# usb-debug.net
KiCad netlist of a schematic drawn in Altium Designer
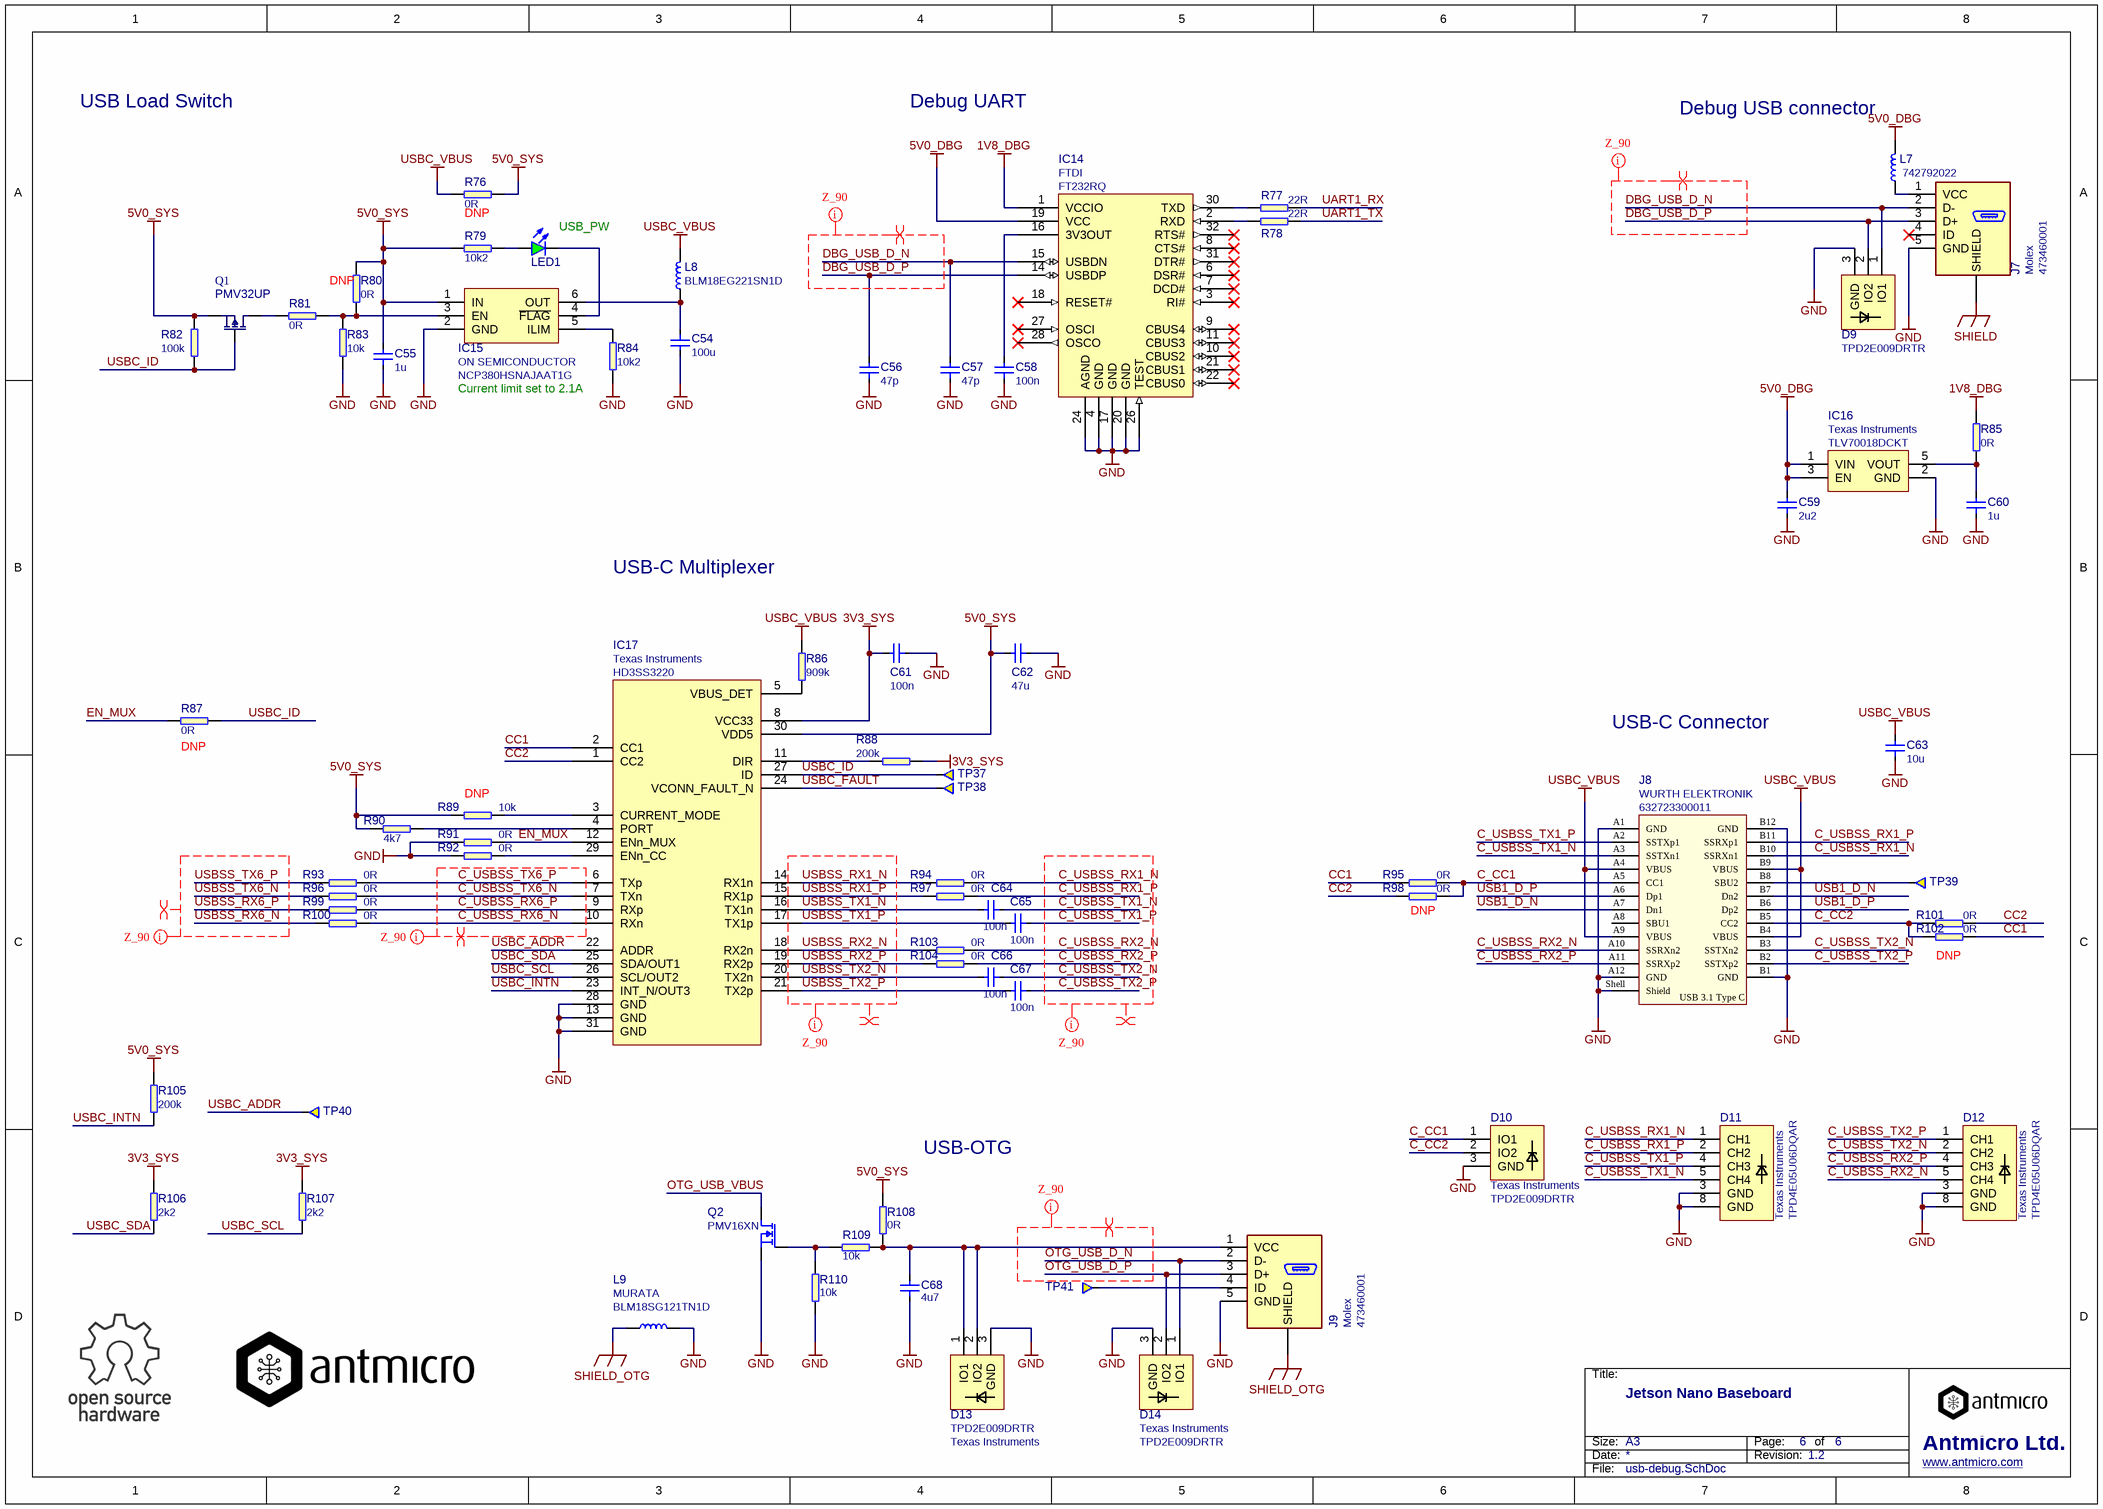
[diagram p0: usb-debug.SchDoc]

(export (version "E")
  (design (tool "Eeschema 10.0.6"))
  (components
    (comp (ref "C54")
      (value "100u")
      (footprint "1210")
      (description "MLCC SMT Capacitor 100uF 1210")
      (fields (field (name "MANUFACTURER") "SAMSUNG") (field (name "PARTNUMBER") "C_100u_1210"))
      (libsource (lib "jetson-nano-baseboard") (part "C_100u_1210"))
    )
    (comp (ref "C55")
      (value "1u")
      (footprint "0603")
      (description "MLCC SMT Capacitor 1uF 0603")
      (fields (field (name "MANUFACTURER") "KEMET") (field (name "PARTNUMBER") "C_1u_0603"))
      (libsource (lib "jetson-nano-baseboard") (part "C_1u_0603"))
    )
    (comp (ref "C56")
      (value "47p")
      (footprint "0603")
      (description "MLCC SMT Capacitor 47pF 0603")
      (fields (field (name "MANUFACTURER") "AVX") (field (name "PARTNUMBER") "C_47p_0603"))
      (libsource (lib "jetson-nano-baseboard") (part "C_47p_0603"))
    )
    (comp (ref "C57")
      (value "47p")
      (footprint "0603")
      (description "MLCC SMT Capacitor 47pF 0603")
      (fields (field (name "MANUFACTURER") "AVX") (field (name "PARTNUMBER") "C_47p_0603"))
      (libsource (lib "jetson-nano-baseboard") (part "C_47p_0603"))
    )
    (comp (ref "C58")
      (value "100n")
      (footprint "0603")
      (description "MLCC SMT Capacitor 100nF 0603")
      (fields (field (name "MANUFACTURER") "AVX") (field (name "PARTNUMBER") "C_100n_0603"))
      (libsource (lib "jetson-nano-baseboard") (part "C_100n_0603"))
    )
    (comp (ref "C59")
      (value "2u2")
      (footprint "0402")
      (description "MLCC SMT Capacitor 2.2uF 0402")
      (fields (field (name "MANUFACTURER") "TDK") (field (name "PARTNUMBER") "C_2u2_0402"))
      (libsource (lib "jetson-nano-baseboard") (part "C_2u2_0402"))
    )
    (comp (ref "C60")
      (value "1u")
      (footprint "0402")
      (description "MLCC SMT Capacitor 1uF 0402")
      (fields (field (name "MANUFACTURER") "MULTICOMP") (field (name "PARTNUMBER") "C_1u_0402"))
      (libsource (lib "jetson-nano-baseboard") (part "C_1u_0402"))
    )
    (comp (ref "C61")
      (value "100n")
      (footprint "0603")
      (description "MLCC SMT Capacitor 100nF 0603")
      (fields (field (name "MANUFACTURER") "AVX") (field (name "PARTNUMBER") "C_100n_0603"))
      (libsource (lib "jetson-nano-baseboard") (part "C_100n_0603"))
    )
    (comp (ref "C62")
      (value "47u")
      (footprint "0805")
      (description "MLCC SMT Capacitor 47uF 0805")
      (fields (field (name "PARTNUMBER") "C_47u_0805") (field (name "MANUFACTURER") "KEMET"))
      (libsource (lib "jetson-nano-baseboard") (part "C_47u_0805"))
    )
    (comp (ref "C63")
      (value "10u")
      (footprint "0603")
      (description "MLCC SMT Capacitor 10uF 0603")
      (fields (field (name "PARTNUMBER") "C_10u_0603") (field (name "MANUFACTURER") "Walsin"))
      (libsource (lib "jetson-nano-baseboard") (part "C_10u_0603"))
    )
    (comp (ref "C64")
      (value "100n")
      (footprint "0402")
      (description "MLCC SMT Capacitor 100n 0402")
      (fields (field (name "MANUFACTURER") "TDK") (field (name "PARTNUMBER") "C_100n_0402"))
      (libsource (lib "jetson-nano-baseboard") (part "C_100n_0402"))
    )
    (comp (ref "C65")
      (value "100n")
      (footprint "0402")
      (description "MLCC SMT Capacitor 100n 0402")
      (fields (field (name "MANUFACTURER") "TDK") (field (name "PARTNUMBER") "C_100n_0402"))
      (libsource (lib "jetson-nano-baseboard") (part "C_100n_0402"))
    )
    (comp (ref "C66")
      (value "100n")
      (footprint "0402")
      (description "MLCC SMT Capacitor 100n 0402")
      (fields (field (name "MANUFACTURER") "TDK") (field (name "PARTNUMBER") "C_100n_0402"))
      (libsource (lib "jetson-nano-baseboard") (part "C_100n_0402"))
    )
    (comp (ref "C67")
      (value "100n")
      (footprint "0402")
      (description "MLCC SMT Capacitor 100n 0402")
      (fields (field (name "MANUFACTURER") "TDK") (field (name "PARTNUMBER") "C_100n_0402"))
      (libsource (lib "jetson-nano-baseboard") (part "C_100n_0402"))
    )
    (comp (ref "C68")
      (value "4u7")
      (footprint "0603")
      (description "MLCC SMT Capacitor 4.7uF 0603")
      (fields (field (name "PARTNUMBER") "C_4u7_0603") (field (name "MANUFACTURER") "MULTICOMP"))
      (libsource (lib "jetson-nano-baseboard") (part "C_4u7_0603"))
    )
    (comp (ref "D9")
      (value "TPD2E009DRTR")
      (footprint "SOT-3")
      (description "ESD Suppressors 2-CH")
      (fields (field (name "MANUFACTURER") "Texas Instruments"))
      (libsource (lib "") (part "TPD2E009_2"))
    )
    (comp (ref "D10")
      (value "TPD2E009DRTR")
      (footprint "SOT-3")
      (description "ESD Suppressors 2-CH")
      (fields (field (name "MANUFACTURER") "Texas Instruments"))
      (libsource (lib "") (part "TPD2E009_1"))
    )
    (comp (ref "D11")
      (value "TPD4E05U06")
      (footprint "TPD4E05U06_PASS")
      (description "ESD Suppressors 4-CH")
      (fields
        (field (name "PARTNUMBER") "TPD4E05U06_PASS")
        (field (name "MANUFACTURER") "Texas Instruments")
        (field (name "PARTSYMBOL") "TPD4E05U06DQAR")
      )
      (libsource (lib "jetson-nano-baseboard") (part "TPD4E05U06"))
    )
    (comp (ref "D12")
      (value "TPD4E05U06")
      (footprint "TPD4E05U06_PASS")
      (description "ESD Suppressors 4-CH")
      (fields
        (field (name "PARTNUMBER") "TPD4E05U06_PASS")
        (field (name "MANUFACTURER") "Texas Instruments")
        (field (name "PARTSYMBOL") "TPD4E05U06DQAR")
      )
      (libsource (lib "jetson-nano-baseboard") (part "TPD4E05U06"))
    )
    (comp (ref "D13")
      (value "TPD2E009DRTR")
      (footprint "SOT-3")
      (description "ESD Suppressors 2-CH")
      (fields (field (name "MANUFACTURER") "Texas Instruments"))
      (libsource (lib "jetson-nano-baseboard") (part "TPD2E009"))
    )
    (comp (ref "D14")
      (value "TPD2E009DRTR")
      (footprint "SOT-3")
      (description "ESD Suppressors 2-CH")
      (fields (field (name "MANUFACTURER") "Texas Instruments"))
      (libsource (lib "") (part "TPD2E009_2"))
    )
    (comp (ref "IC14")
      (value "FT232RQ")
      (footprint "QFN-32")
      (description "USB to serial UART interface")
      (fields (field (name "MANUFACTURER") "FTDI") (field (name "PARTNUMBER") "FT232RQ"))
      (libsource (lib "jetson-nano-baseboard") (part "FT232RQ"))
    )
    (comp (ref "IC15")
      (value "NCP380HSNAJAAT1G")
      (footprint "TSOP-6")
      (description "POWER LOAD SWITCH, HIGH SIDE")
      (fields (field (name "MANUFACTURER") "ON SEMICONDUCTOR"))
      (libsource (lib "jetson-nano-baseboard") (part "NCP380HSNAJAAT1G"))
    )
    (comp (ref "IC16")
      (value "TLV70018DCKT")
      (footprint "SC70-5")
      (description "Voltage Regulator, 2V to 5.5V, 175mV Dropout, 1.8Vout, 200mAout")
      (fields (field (name "MANUFACTURER") "Texas Instruments"))
      (libsource (lib "jetson-nano-baseboard") (part "TLV700"))
    )
    (comp (ref "IC17")
      (value "HD3SS3220")
      (footprint "RNH0030A")
      (description "IC DRP PORT CTLR USB-C 30WQFN")
      (fields (field (name "MANUFACTURER") "Texas Instruments"))
      (libsource (lib "jetson-nano-baseboard") (part "HD3SS3220"))
    )
    (comp (ref "J7")
      (value "Molex 47346-0001")
      (footprint "CON-Molex-047346-0001")
      (description "USB - micro B Receptacle Connector 5 Position Surface Mount, Right Angle, Horizontal")
      (fields
        (field (name "PARTNUMBER") "CON-Molex-47346-0001")
        (field (name "MANUFACTURER") "Molex")
        (field (name "PARTSYMBOL") "473460001")
      )
      (libsource (lib "jetson-nano-baseboard") (part "Micro USB B"))
    )
    (comp (ref "J8")
      (value "632723300011")
      (footprint "WE_632723300011")
      (description "USB 3.1 Type C Receptacle Horizontal THR WR-COM")
      (fields (field (name "PARTNUMBER") "WE_632723300011") (field (name "MANUFACTURER") "WURTH ELEKTRONIK"))
      (libsource (lib "jetson-nano-baseboard") (part "WE_632723300011"))
    )
    (comp (ref "J9")
      (value "Molex 47346-0001")
      (footprint "CON-Molex-047346-0001")
      (description "USB - micro B Receptacle Connector 5 Position Surface Mount, Right Angle, Horizontal")
      (fields
        (field (name "PARTNUMBER") "CON-Molex-47346-0001")
        (field (name "MANUFACTURER") "Molex")
        (field (name "PARTSYMBOL") "473460001")
      )
      (libsource (lib "jetson-nano-baseboard") (part "Micro USB B"))
    )
    (comp (ref "L7")
      (value "742792022")
      (footprint "0805")
      (description "MURATA  BLM18EG221SN1D  FERRITE BEAD, 0.05OHM, 2A, 0603")
      (fields (field (name "MANUFACTURER") "WURTH ELEKTRONIK"))
      (libsource (lib "jetson-nano-baseboard") (part "742792022"))
    )
    (comp (ref "L8")
      (value "BLM18EG221SN1D")
      (footprint "0603")
      (description "MURATA  BLM18EG221SN1D  FERRITE BEAD, 0.05OHM, 2A, 0603")
      (fields (field (name "MANUFACTURER") "MURATA"))
      (libsource (lib "jetson-nano-baseboard") (part "BLM18EG221SN1D"))
    )
    (comp (ref "L9")
      (value "BLM18SG121TN1D")
      (footprint "0603")
      (description "FERRITE BEAD, 0.025OHM, 3A, 0603")
      (fields (field (name "MANUFACTURER") "MURATA"))
      (libsource (lib "jetson-nano-baseboard") (part "BLM18SG121TN1D"))
    )
    (comp (ref "LED1")
      (value "KPT-1608SGC")
      (footprint "LED0603")
      (description "LED Green 0603 case")
      (fields (field (name "MANUFACTURER") "KINGBRIGHT") (field (name "PARTNUMBER") "LED_G"))
      (libsource (lib "jetson-nano-baseboard") (part "LED"))
    )
    (comp (ref "Q1")
      (value "PMV32UP")
      (footprint "SOT-23")
      (description "P CH, 20V, 4A")
      (fields (field (name "MANUFACTURER") "NXP"))
      (libsource (lib "jetson-nano-baseboard") (part "PMOS"))
    )
    (comp (ref "Q2")
      (value "PMV16XN")
      (footprint "SOT-23")
      (description "MOSFET, N CH")
      (fields (field (name "MANUFACTURER") "NXP"))
      (libsource (lib "jetson-nano-baseboard") (part "NMOS_PMV16XN"))
    )
    (comp (ref "R76")
      (value "0R")
      (footprint "0603")
      (description "RES, 0R, 0603")
      (fields (field (name "MANUFACTURER") "BOURNS") (field (name "PARTNUMBER") "R_0R_0603"))
      (libsource (lib "jetson-nano-baseboard") (part "R_0R_0603"))
    )
    (comp (ref "R77")
      (value "22R")
      (footprint "0402")
      (description "RES, 22R, 0402")
      (fields (field (name "MANUFACTURER") "VISHAY") (field (name "PARTNUMBER") "R_22R_0402"))
      (libsource (lib "jetson-nano-baseboard") (part "R_22R_0402"))
    )
    (comp (ref "R78")
      (value "22R")
      (footprint "0402")
      (description "RES, 22R, 0402")
      (fields (field (name "MANUFACTURER") "VISHAY") (field (name "PARTNUMBER") "R_22R_0402"))
      (libsource (lib "jetson-nano-baseboard") (part "R_22R_0402"))
    )
    (comp (ref "R79")
      (value "10k2")
      (footprint "0603")
      (description "RES, 470R, 0603")
      (fields (field (name "MANUFACTURER") "BOURNS") (field (name "PARTNUMBER") "R_470R_0603"))
      (libsource (lib "jetson-nano-baseboard") (part "R_470R_0603"))
    )
    (comp (ref "R80")
      (value "0R")
      (footprint "0402")
      (description "RES, 0R, 0402")
      (fields (field (name "PARTNUMBER") "R_0R_0402") (field (name "MANUFACTURER") "Panasonic"))
      (libsource (lib "") (part "R_0R_0402_1"))
    )
    (comp (ref "R81")
      (value "0R")
      (footprint "0402")
      (description "RES, 0R, 0402")
      (fields (field (name "PARTNUMBER") "R_0R_0402") (field (name "MANUFACTURER") "Panasonic"))
      (libsource (lib "jetson-nano-baseboard") (part "R_0R_0402"))
    )
    (comp (ref "R82")
      (value "100k")
      (footprint "0603")
      (description "RES, 100k, 0603")
      (fields (field (name "MANUFACTURER") "BOURNS") (field (name "PARTNUMBER") "R_100k_0603"))
      (libsource (lib "jetson-nano-baseboard") (part "R_100k_0603"))
    )
    (comp (ref "R83")
      (value "10k")
      (footprint "0402")
      (description "RES, 10k, 0402")
      (fields (field (name "MANUFACTURER") "MULTICOMP") (field (name "PARTNUMBER") "R_10k_0402"))
      (libsource (lib "") (part "R_10k_0402_2"))
    )
    (comp (ref "R84")
      (value "10k2")
      (footprint "0603")
      (description "RES, 5k6, 0603")
      (fields (field (name "PARTNUMBER") "R_5k6_0603") (field (name "MANUFACTURER") "Panasonic"))
      (libsource (lib "jetson-nano-baseboard") (part "R_5k6_0603"))
    )
    (comp (ref "R85")
      (value "0R")
      (footprint "0603")
      (description "RES, 0R, 0603")
      (fields (field (name "MANUFACTURER") "BOURNS") (field (name "PARTNUMBER") "R_0R_0603"))
      (libsource (lib "") (part "R_0R_0603_1"))
    )
    (comp (ref "R86")
      (value "909k")
      (footprint "0402")
      (description "RES, 909k, 0402")
      (fields (field (name "PARTNUMBER") "R_909k_0402") (field (name "MANUFACTURER") "Panasonic"))
      (libsource (lib "jetson-nano-baseboard") (part "R_909k_0402"))
    )
    (comp (ref "R87")
      (value "0R")
      (footprint "0402")
      (description "RES, 0R, 0402")
      (fields (field (name "PARTNUMBER") "R_0R_0402") (field (name "MANUFACTURER") "Panasonic"))
      (libsource (lib "jetson-nano-baseboard") (part "R_0R_0402"))
    )
    (comp (ref "R88")
      (value "200k")
      (footprint "0402")
      (description "RES, 200k, 0402")
      (fields (field (name "PARTNUMBER") "R_200k_0402") (field (name "MANUFACTURER") "YAGEO"))
      (libsource (lib "") (part "R_200k_0402_1"))
    )
    (comp (ref "R89")
      (value "10k")
      (footprint "0402")
      (description "RES, 10k, 0402")
      (fields (field (name "PARTNUMBER") "R_10k_0402") (field (name "MANUFACTURER") "MULTICOMP"))
      (libsource (lib "") (part "R_10k_0402_1"))
    )
    (comp (ref "R90")
      (value "4k7")
      (footprint "0402")
      (description "RES, 4k7, 0402")
      (fields (field (name "PARTNUMBER") "R_4k7_0402") (field (name "MANUFACTURER") "Panasonic"))
      (libsource (lib "jetson-nano-baseboard") (part "R_4k7_0402"))
    )
    (comp (ref "R91")
      (value "0R")
      (footprint "0402")
      (description "RES, 0R, 0402")
      (fields (field (name "PARTNUMBER") "R_0R_0402") (field (name "MANUFACTURER") "Panasonic"))
      (libsource (lib "jetson-nano-baseboard") (part "R_0R_0402"))
    )
    (comp (ref "R92")
      (value "0R")
      (footprint "0402")
      (description "RES, 0R, 0402")
      (fields (field (name "PARTNUMBER") "R_0R_0402") (field (name "MANUFACTURER") "Panasonic"))
      (libsource (lib "jetson-nano-baseboard") (part "R_0R_0402"))
    )
    (comp (ref "R93")
      (value "0R")
      (footprint "0402")
      (description "RES, 0R, 0402")
      (fields (field (name "PARTNUMBER") "R_0R_0402") (field (name "MANUFACTURER") "Panasonic"))
      (libsource (lib "jetson-nano-baseboard") (part "R_0R_0402"))
    )
    (comp (ref "R94")
      (value "0R")
      (footprint "0402")
      (description "RES, 0R, 0402")
      (fields (field (name "PARTNUMBER") "R_0R_0402") (field (name "MANUFACTURER") "Panasonic"))
      (libsource (lib "jetson-nano-baseboard") (part "R_0R_0402"))
    )
    (comp (ref "R95")
      (value "0R")
      (footprint "0402")
      (description "RES, 0R, 0402")
      (fields (field (name "PARTNUMBER") "R_0R_0402") (field (name "MANUFACTURER") "Panasonic"))
      (libsource (lib "jetson-nano-baseboard") (part "R_0R_0402"))
    )
    (comp (ref "R96")
      (value "0R")
      (footprint "0402")
      (description "RES, 0R, 0402")
      (fields (field (name "PARTNUMBER") "R_0R_0402") (field (name "MANUFACTURER") "Panasonic"))
      (libsource (lib "jetson-nano-baseboard") (part "R_0R_0402"))
    )
    (comp (ref "R97")
      (value "0R")
      (footprint "0402")
      (description "RES, 0R, 0402")
      (fields (field (name "PARTNUMBER") "R_0R_0402") (field (name "MANUFACTURER") "Panasonic"))
      (libsource (lib "jetson-nano-baseboard") (part "R_0R_0402"))
    )
    (comp (ref "R98")
      (value "0R")
      (footprint "0402")
      (description "RES, 0R, 0402")
      (fields (field (name "PARTNUMBER") "R_0R_0402") (field (name "MANUFACTURER") "Panasonic"))
      (libsource (lib "jetson-nano-baseboard") (part "R_0R_0402"))
    )
    (comp (ref "R99")
      (value "0R")
      (footprint "0402")
      (description "RES, 0R, 0402")
      (fields (field (name "PARTNUMBER") "R_0R_0402") (field (name "MANUFACTURER") "Panasonic"))
      (libsource (lib "jetson-nano-baseboard") (part "R_0R_0402"))
    )
    (comp (ref "R100")
      (value "0R")
      (footprint "0402")
      (description "RES, 0R, 0402")
      (fields (field (name "PARTNUMBER") "R_0R_0402") (field (name "MANUFACTURER") "Panasonic"))
      (libsource (lib "jetson-nano-baseboard") (part "R_0R_0402"))
    )
    (comp (ref "R101")
      (value "0R")
      (footprint "0402")
      (description "RES, 0R, 0402")
      (fields (field (name "PARTNUMBER") "R_0R_0402") (field (name "MANUFACTURER") "Panasonic"))
      (libsource (lib "jetson-nano-baseboard") (part "R_0R_0402"))
    )
    (comp (ref "R102")
      (value "0R")
      (footprint "0402")
      (description "RES, 0R, 0402")
      (fields (field (name "PARTNUMBER") "R_0R_0402") (field (name "MANUFACTURER") "Panasonic"))
      (libsource (lib "jetson-nano-baseboard") (part "R_0R_0402"))
    )
    (comp (ref "R103")
      (value "0R")
      (footprint "0402")
      (description "RES, 0R, 0402")
      (fields (field (name "PARTNUMBER") "R_0R_0402") (field (name "MANUFACTURER") "Panasonic"))
      (libsource (lib "jetson-nano-baseboard") (part "R_0R_0402"))
    )
    (comp (ref "R104")
      (value "0R")
      (footprint "0402")
      (description "RES, 0R, 0402")
      (fields (field (name "PARTNUMBER") "R_0R_0402") (field (name "MANUFACTURER") "Panasonic"))
      (libsource (lib "jetson-nano-baseboard") (part "R_0R_0402"))
    )
    (comp (ref "R105")
      (value "200k")
      (footprint "0402")
      (description "RES, 200k, 0402")
      (fields (field (name "PARTNUMBER") "R_200k_0402") (field (name "MANUFACTURER") "YAGEO"))
      (libsource (lib "jetson-nano-baseboard") (part "R_200k_0402"))
    )
    (comp (ref "R106")
      (value "2k2")
      (footprint "0402")
      (description "RES, 2k2, 0402")
      (fields (field (name "PARTNUMBER") "R_2k2_0402") (field (name "MANUFACTURER") "MULTICOMP"))
      (libsource (lib "jetson-nano-baseboard") (part "R_2k2_0402"))
    )
    (comp (ref "R107")
      (value "2k2")
      (footprint "0402")
      (description "RES, 2k2, 0402")
      (fields (field (name "PARTNUMBER") "R_2k2_0402") (field (name "MANUFACTURER") "MULTICOMP"))
      (libsource (lib "jetson-nano-baseboard") (part "R_2k2_0402"))
    )
    (comp (ref "R108")
      (value "0R")
      (footprint "0402")
      (description "RES, 0R, 0402")
      (fields (field (name "PARTNUMBER") "R_0R_0402") (field (name "MANUFACTURER") "Panasonic"))
      (libsource (lib "jetson-nano-baseboard") (part "R_0R_0402"))
    )
    (comp (ref "R109")
      (value "10k")
      (footprint "0402")
      (description "RES, 10k, 0402")
      (fields (field (name "PARTNUMBER") "R_10k_0402") (field (name "MANUFACTURER") "MULTICOMP"))
      (libsource (lib "jetson-nano-baseboard") (part "R_10k_0402"))
    )
    (comp (ref "R110")
      (value "10k")
      (footprint "0402")
      (description "RES, 10k, 0402")
      (fields (field (name "PARTNUMBER") "R_10k_0402") (field (name "MANUFACTURER") "MULTICOMP"))
      (libsource (lib "") (part "R_10k_0402_1"))
    )
    (comp (ref "TP37")
      (value "Testpad")
      (footprint "TP-R-1.5")
      (description "Testpad, round, 1.5mm")
      (fields (field (name "PARTNUMBER") "TP-R-1.5"))
      (libsource (lib "jetson-nano-baseboard") (part "Testpad"))
    )
    (comp (ref "TP38")
      (value "Testpad")
      (footprint "TP-R-1.5")
      (description "Testpad, round, 1.5mm")
      (fields (field (name "PARTNUMBER") "TP-R-1.5"))
      (libsource (lib "jetson-nano-baseboard") (part "Testpad"))
    )
    (comp (ref "TP39")
      (value "Testpad")
      (footprint "TP-R-1.5")
      (description "Testpad, round, 1.5mm")
      (fields (field (name "PARTNUMBER") "TP-R-1.5"))
      (libsource (lib "jetson-nano-baseboard") (part "Testpad"))
    )
    (comp (ref "TP40")
      (value "Testpad")
      (footprint "TP-R-1.5")
      (description "Testpad, round, 1.5mm")
      (fields (field (name "PARTNUMBER") "TP-R-1.5"))
      (libsource (lib "jetson-nano-baseboard") (part "Testpad"))
    )
    (comp (ref "TP41")
      (value "Testpad")
      (footprint "TP-R-1.5")
      (description "Testpad, round, 1.5mm")
      (fields (field (name "PARTNUMBER") "TP-R-1.5"))
      (libsource (lib "jetson-nano-baseboard") (part "Testpad"))
    )
  )
  (nets
    (net (code "1") (name "/CC1") (class "Default")
      (node (ref "IC17") (pin "2") (pinfunction "CC1_2") (pintype "passive"))
      (node (ref "R102") (pin "2") (pintype "passive"))
      (node (ref "R95") (pin "1") (pintype "passive"))
    )
    (net (code "2") (name "/CC2") (class "Default")
      (node (ref "IC17") (pin "1") (pinfunction "CC2_1") (pintype "passive"))
      (node (ref "R101") (pin "2") (pintype "passive"))
      (node (ref "R98") (pin "1") (pintype "passive"))
    )
    (net (code "3") (name "/C_CC1") (class "Default")
      (node (ref "D10") (pin "1") (pinfunction "IO1_1") (pintype "passive"))
      (node (ref "J8") (pin "A5") (pinfunction "CC1_A5") (pintype "passive"))
      (node (ref "R95") (pin "2") (pintype "passive"))
      (node (ref "R98") (pin "2") (pintype "passive"))
    )
    (net (code "4") (name "/C_CC2") (class "Default")
      (node (ref "D10") (pin "2") (pinfunction "IO2_2") (pintype "passive"))
      (node (ref "J8") (pin "B5") (pinfunction "CC2_B5") (pintype "passive"))
      (node (ref "R101") (pin "1") (pintype "passive"))
      (node (ref "R102") (pin "1") (pintype "passive"))
    )
    (net (code "5") (name "/C_USBSS_RX1_N") (class "Default")
      (node (ref "D11") (pin "1") (pinfunction "CH1_1") (pintype "passive"))
      (node (ref "J8") (pin "B10") (pinfunction "SSRXn1_B10") (pintype "passive"))
      (node (ref "R94") (pin "2") (pintype "passive"))
    )
    (net (code "6") (name "/C_USBSS_RX1_P") (class "Default")
      (node (ref "D11") (pin "2") (pinfunction "CH2_2") (pintype "passive"))
      (node (ref "J8") (pin "B11") (pinfunction "SSRXp1_B11") (pintype "passive"))
      (node (ref "R97") (pin "2") (pintype "passive"))
    )
    (net (code "7") (name "/C_USBSS_RX2_N") (class "Default")
      (node (ref "D12") (pin "5") (pinfunction "CH4_5") (pintype "passive"))
      (node (ref "J8") (pin "A10") (pinfunction "SSRXn2_A10") (pintype "passive"))
      (node (ref "R103") (pin "2") (pintype "passive"))
    )
    (net (code "8") (name "/C_USBSS_RX2_P") (class "Default")
      (node (ref "D12") (pin "4") (pinfunction "CH3_4") (pintype "passive"))
      (node (ref "J8") (pin "A11") (pinfunction "SSRXp2_A11") (pintype "passive"))
      (node (ref "R104") (pin "2") (pintype "passive"))
    )
    (net (code "9") (name "/C_USBSS_RX6_N") (class "Default")
      (node (ref "IC17") (pin "10") (pinfunction "RXn_10") (pintype "passive"))
      (node (ref "R100") (pin "2") (pintype "passive"))
    )
    (net (code "10") (name "/C_USBSS_RX6_P") (class "Default")
      (node (ref "IC17") (pin "9") (pinfunction "RXp_9") (pintype "passive"))
      (node (ref "R99") (pin "2") (pintype "passive"))
    )
    (net (code "11") (name "/C_USBSS_TX1_N") (class "Default")
      (node (ref "C64") (pin "1") (pinfunction "1_1") (pintype "passive"))
      (node (ref "D11") (pin "5") (pinfunction "CH4_5") (pintype "passive"))
      (node (ref "J8") (pin "A3") (pinfunction "SSTXn1_A3") (pintype "passive"))
    )
    (net (code "12") (name "/C_USBSS_TX1_P") (class "Default")
      (node (ref "C65") (pin "1") (pinfunction "1_1") (pintype "passive"))
      (node (ref "D11") (pin "4") (pinfunction "CH3_4") (pintype "passive"))
      (node (ref "J8") (pin "A2") (pinfunction "SSTXp1_A2") (pintype "passive"))
    )
    (net (code "13") (name "/C_USBSS_TX2_N") (class "Default")
      (node (ref "C66") (pin "1") (pinfunction "1_1") (pintype "passive"))
      (node (ref "D12") (pin "2") (pinfunction "CH2_2") (pintype "passive"))
      (node (ref "J8") (pin "B3") (pinfunction "SSTXn2_B3") (pintype "passive"))
    )
    (net (code "14") (name "/C_USBSS_TX2_P") (class "Default")
      (node (ref "C67") (pin "1") (pinfunction "1_1") (pintype "passive"))
      (node (ref "D12") (pin "1") (pinfunction "CH1_1") (pintype "passive"))
      (node (ref "J8") (pin "B2") (pinfunction "SSTXp2_B2") (pintype "passive"))
    )
    (net (code "15") (name "/C_USBSS_TX6_N") (class "Default")
      (node (ref "IC17") (pin "7") (pinfunction "TXn_7") (pintype "passive"))
      (node (ref "R96") (pin "2") (pintype "passive"))
    )
    (net (code "16") (name "/C_USBSS_TX6_P") (class "Default")
      (node (ref "IC17") (pin "6") (pinfunction "TXp_6") (pintype "passive"))
      (node (ref "R93") (pin "2") (pintype "passive"))
    )
    (net (code "17") (name "/DBG_USB_D_N") (class "Default")
      (node (ref "C57") (pin "2") (pinfunction "2_2") (pintype "passive"))
      (node (ref "D9") (pin "1") (pinfunction "IO1_1") (pintype "passive"))
      (node (ref "IC14") (pin "15") (pinfunction "USBDN_15") (pintype "bidirectional"))
      (node (ref "J7") (pin "2") (pinfunction "D-_2") (pintype "passive"))
    )
    (net (code "18") (name "/DBG_USB_D_P") (class "Default")
      (node (ref "C56") (pin "2") (pinfunction "2_2") (pintype "passive"))
      (node (ref "D9") (pin "2") (pinfunction "IO2_2") (pintype "passive"))
      (node (ref "IC14") (pin "14") (pinfunction "USBDP_14") (pintype "bidirectional"))
      (node (ref "J7") (pin "3") (pinfunction "D+_3") (pintype "passive"))
    )
    (net (code "19") (name "/EN_MUX") (class "Default")
      (node (ref "IC17") (pin "12") (pinfunction "ENn_MUX_12") (pintype "passive"))
      (node (ref "R87") (pin "1") (pintype "passive"))
      (node (ref "R91") (pin "2") (pintype "passive"))
    )
    (net (code "20") (name "/OTG_USB_D_N") (class "Default")
      (node (ref "D14") (pin "1") (pinfunction "IO1_1") (pintype "passive"))
      (node (ref "J9") (pin "2") (pinfunction "D-_2") (pintype "passive"))
    )
    (net (code "21") (name "/OTG_USB_D_P") (class "Default")
      (node (ref "D14") (pin "2") (pinfunction "IO2_2") (pintype "passive"))
      (node (ref "J9") (pin "3") (pinfunction "D+_3") (pintype "passive"))
    )
    (net (code "22") (name "/OTG_USB_VBUS") (class "Default")
      (node (ref "Q2") (pin "3") (pinfunction "D_3") (pintype "passive"))
    )
    (net (code "23") (name "/UART1_RX") (class "Default") (node (ref "R77") (pin "2") (pintype "passive")))
    (net (code "24") (name "/UART1_TX") (class "Default") (node (ref "R78") (pin "2") (pintype "passive")))
    (net (code "25") (name "/USB1_D_N") (class "Default")
      (node (ref "J8") (pin "A7") (pinfunction "Dn1_A7") (pintype "passive"))
      (node (ref "J8") (pin "B7") (pinfunction "Dn2_B7") (pintype "passive"))
    )
    (net (code "26") (name "/USB1_D_P") (class "Default")
      (node (ref "J8") (pin "A6") (pinfunction "Dp1_A6") (pintype "passive"))
      (node (ref "J8") (pin "B6") (pinfunction "Dp2_B6") (pintype "passive"))
    )
    (net (code "27") (name "/USBC_ADDR") (class "Default")
      (node (ref "IC17") (pin "22") (pinfunction "ADDR_22") (pintype "passive"))
      (node (ref "TP40") (pin "1") (pintype "passive"))
    )
    (net (code "28") (name "/USBC_FAULT") (class "Default")
      (node (ref "IC17") (pin "24") (pinfunction "VCONN_FAULT_N_24") (pintype "passive"))
      (node (ref "TP38") (pin "1") (pintype "passive"))
    )
    (net (code "29") (name "/USBC_ID") (class "Default")
      (node (ref "IC17") (pin "27") (pinfunction "ID_27") (pintype "passive"))
      (node (ref "Q1") (pin "1") (pinfunction "G_1") (pintype "passive"))
      (node (ref "R82") (pin "2") (pintype "passive"))
      (node (ref "R87") (pin "2") (pintype "passive"))
      (node (ref "TP37") (pin "1") (pintype "passive"))
    )
    (net (code "30") (name "/USBC_INTN") (class "Default")
      (node (ref "IC17") (pin "23") (pinfunction "INT_N/OUT3_23") (pintype "passive"))
      (node (ref "R105") (pin "1") (pintype "passive"))
    )
    (net (code "31") (name "/USBC_SCL") (class "Default")
      (node (ref "IC17") (pin "26") (pinfunction "SCL/OUT2_26") (pintype "passive"))
      (node (ref "R107") (pin "1") (pintype "passive"))
    )
    (net (code "32") (name "/USBC_SDA") (class "Default")
      (node (ref "IC17") (pin "25") (pinfunction "SDA/OUT1_25") (pintype "passive"))
      (node (ref "R106") (pin "1") (pintype "passive"))
    )
    (net (code "33") (name "/USBSS_RX1_N") (class "Default")
      (node (ref "IC17") (pin "14") (pinfunction "RX1n_14") (pintype "passive"))
      (node (ref "R94") (pin "1") (pintype "passive"))
    )
    (net (code "34") (name "/USBSS_RX1_P") (class "Default")
      (node (ref "IC17") (pin "15") (pinfunction "RX1p_15") (pintype "passive"))
      (node (ref "R97") (pin "1") (pintype "passive"))
    )
    (net (code "35") (name "/USBSS_RX2_N") (class "Default")
      (node (ref "IC17") (pin "18") (pinfunction "RX2n_18") (pintype "passive"))
      (node (ref "R103") (pin "1") (pintype "passive"))
    )
    (net (code "36") (name "/USBSS_RX2_P") (class "Default")
      (node (ref "IC17") (pin "19") (pinfunction "RX2p_19") (pintype "passive"))
      (node (ref "R104") (pin "1") (pintype "passive"))
    )
    (net (code "37") (name "/USBSS_RX6_N") (class "Default")
      (node (ref "R100") (pin "1") (pintype "passive"))
    )
    (net (code "38") (name "/USBSS_RX6_P") (class "Default") (node (ref "R99") (pin "1") (pintype "passive")))
    (net (code "39") (name "/USBSS_TX1_N") (class "Default")
      (node (ref "C64") (pin "2") (pinfunction "2_2") (pintype "passive"))
      (node (ref "IC17") (pin "16") (pinfunction "TX1n_16") (pintype "passive"))
    )
    (net (code "40") (name "/USBSS_TX1_P") (class "Default")
      (node (ref "C65") (pin "2") (pinfunction "2_2") (pintype "passive"))
      (node (ref "IC17") (pin "17") (pinfunction "TX1p_17") (pintype "passive"))
    )
    (net (code "41") (name "/USBSS_TX2_N") (class "Default")
      (node (ref "C66") (pin "2") (pinfunction "2_2") (pintype "passive"))
      (node (ref "IC17") (pin "20") (pinfunction "TX2n_20") (pintype "passive"))
    )
    (net (code "42") (name "/USBSS_TX2_P") (class "Default")
      (node (ref "C67") (pin "2") (pinfunction "2_2") (pintype "passive"))
      (node (ref "IC17") (pin "21") (pinfunction "TX2p_21") (pintype "passive"))
    )
    (net (code "43") (name "/USBSS_TX6_N") (class "Default") (node (ref "R96") (pin "1") (pintype "passive")))
    (net (code "44") (name "/USBSS_TX6_P") (class "Default") (node (ref "R93") (pin "1") (pintype "passive")))
    (net (code "45") (name "1V8_DBG") (class "Default")
      (node (ref "IC14") (pin "1") (pinfunction "VCCIO_1") (pintype "power_in"))
      (node (ref "R85") (pin "2") (pintype "passive"))
    )
    (net (code "46") (name "3V3_SYS") (class "Default")
      (node (ref "C61") (pin "2") (pinfunction "2_2") (pintype "passive"))
      (node (ref "IC17") (pin "8") (pinfunction "VCC33_8") (pintype "passive"))
      (node (ref "R106") (pin "2") (pintype "passive"))
      (node (ref "R107") (pin "2") (pintype "passive"))
      (node (ref "R88") (pin "2") (pintype "passive"))
    )
    (net (code "47") (name "5V0_DBG") (class "Default")
      (node (ref "C59") (pin "2") (pinfunction "2_2") (pintype "passive"))
      (node (ref "IC14") (pin "19") (pinfunction "VCC_19") (pintype "power_in"))
      (node (ref "IC16") (pin "1") (pinfunction "VIN_1") (pintype "passive"))
      (node (ref "IC16") (pin "3") (pinfunction "EN_3") (pintype "passive"))
      (node (ref "L7") (pin "2") (pintype "passive"))
    )
    (net (code "48") (name "5V0_SYS") (class "Default")
      (node (ref "C55") (pin "2") (pinfunction "2_2") (pintype "passive"))
      (node (ref "C62") (pin "2") (pinfunction "2_2") (pintype "passive"))
      (node (ref "IC15") (pin "1") (pinfunction "IN_1") (pintype "passive"))
      (node (ref "IC17") (pin "30") (pinfunction "VDD5_30") (pintype "passive"))
      (node (ref "Q1") (pin "2") (pinfunction "S_2") (pintype "passive"))
      (node (ref "R105") (pin "2") (pintype "passive"))
      (node (ref "R108") (pin "2") (pintype "passive"))
      (node (ref "R76") (pin "2") (pintype "passive"))
      (node (ref "R79") (pin "2") (pintype "passive"))
      (node (ref "R80") (pin "2") (pintype "passive"))
      (node (ref "R82") (pin "1") (pintype "passive"))
      (node (ref "R89") (pin "1") (pintype "passive"))
      (node (ref "R90") (pin "1") (pintype "passive"))
    )
    (net (code "49") (name "GND") (class "Default")
      (node (ref "C54") (pin "2") (pinfunction "2_2") (pintype "passive"))
      (node (ref "C55") (pin "1") (pinfunction "1_1") (pintype "passive"))
      (node (ref "C56") (pin "1") (pinfunction "1_1") (pintype "passive"))
      (node (ref "C57") (pin "1") (pinfunction "1_1") (pintype "passive"))
      (node (ref "C58") (pin "1") (pinfunction "1_1") (pintype "passive"))
      (node (ref "C59") (pin "1") (pinfunction "1_1") (pintype "passive"))
      (node (ref "C60") (pin "1") (pinfunction "1_1") (pintype "passive"))
      (node (ref "C61") (pin "1") (pinfunction "1_1") (pintype "passive"))
      (node (ref "C62") (pin "1") (pinfunction "1_1") (pintype "passive"))
      (node (ref "C63") (pin "1") (pinfunction "1_1") (pintype "passive"))
      (node (ref "C68") (pin "1") (pinfunction "1_1") (pintype "passive"))
      (node (ref "D10") (pin "3") (pinfunction "GND_3") (pintype "passive"))
      (node (ref "D11") (pin "3") (pinfunction "GND_3") (pintype "passive"))
      (node (ref "D11") (pin "8") (pinfunction "GND_8") (pintype "passive"))
      (node (ref "D12") (pin "3") (pinfunction "GND_3") (pintype "passive"))
      (node (ref "D12") (pin "8") (pinfunction "GND_8") (pintype "passive"))
      (node (ref "D13") (pin "3") (pinfunction "GND_3") (pintype "passive"))
      (node (ref "D14") (pin "3") (pinfunction "GND_3") (pintype "passive"))
      (node (ref "D9") (pin "3") (pinfunction "GND_3") (pintype "passive"))
      (node (ref "IC14") (pin "17") (pinfunction "GND_17") (pintype "power_in"))
      (node (ref "IC14") (pin "20") (pinfunction "GND_20") (pintype "power_in"))
      (node (ref "IC14") (pin "24") (pinfunction "AGND_24") (pintype "power_in"))
      (node (ref "IC14") (pin "26") (pinfunction "TEST_26") (pintype "input"))
      (node (ref "IC14") (pin "4") (pinfunction "GND_4") (pintype "power_in"))
      (node (ref "IC15") (pin "2") (pinfunction "GND_2") (pintype "passive"))
      (node (ref "IC16") (pin "2") (pinfunction "GND_2") (pintype "passive"))
      (node (ref "IC17") (pin "13") (pinfunction "GND_13") (pintype "passive"))
      (node (ref "IC17") (pin "28") (pinfunction "GND_28") (pintype "passive"))
      (node (ref "IC17") (pin "31") (pinfunction "GND_31") (pintype "passive"))
      (node (ref "J7") (pin "5") (pinfunction "GND_5") (pintype "power_in"))
      (node (ref "J8") (pin "A1") (pinfunction "GND_A1") (pintype "passive"))
      (node (ref "J8") (pin "A12") (pinfunction "GND_A12") (pintype "passive"))
      (node (ref "J8") (pin "B1") (pinfunction "GND_B1") (pintype "passive"))
      (node (ref "J8") (pin "B12") (pinfunction "GND_B12") (pintype "passive"))
      (node (ref "J8") (pin "Shell") (pinfunction "Shield_Shell") (pintype "passive"))
      (node (ref "J9") (pin "5") (pinfunction "GND_5") (pintype "power_in"))
      (node (ref "L9") (pin "2") (pintype "passive"))
      (node (ref "Q2") (pin "2") (pinfunction "S_2") (pintype "passive"))
      (node (ref "R110") (pin "1") (pintype "passive"))
      (node (ref "R83") (pin "1") (pintype "passive"))
      (node (ref "R84") (pin "1") (pintype "passive"))
      (node (ref "R91") (pin "1") (pintype "passive"))
      (node (ref "R92") (pin "1") (pintype "passive"))
    )
    (net (code "50") (name "Net-(D13-IO1)") (class "Default")
      (node (ref "C68") (pin "2") (pinfunction "2_2") (pintype "passive"))
      (node (ref "D13") (pin "1") (pinfunction "IO1_1") (pintype "passive"))
      (node (ref "D13") (pin "2") (pinfunction "IO2_2") (pintype "passive"))
      (node (ref "J9") (pin "1") (pinfunction "VCC_1") (pintype "power_in"))
      (node (ref "R108") (pin "1") (pintype "passive"))
      (node (ref "R109") (pin "1") (pintype "passive"))
    )
    (net (code "51") (name "Net-(IC14-3V3OUT)") (class "Default")
      (node (ref "C58") (pin "2") (pinfunction "2_2") (pintype "passive"))
      (node (ref "IC14") (pin "16") (pinfunction "3V3OUT_16") (pintype "power_in"))
    )
    (net (code "52") (name "Net-(IC14-RXD)") (class "Default")
      (node (ref "IC14") (pin "2") (pinfunction "RXD_2") (pintype "input"))
      (node (ref "R78") (pin "1") (pintype "passive"))
    )
    (net (code "53") (name "Net-(IC14-TXD)") (class "Default")
      (node (ref "IC14") (pin "30") (pinfunction "TXD_30") (pintype "output"))
      (node (ref "R77") (pin "1") (pintype "passive"))
    )
    (net (code "54") (name "Net-(IC15-EN)") (class "Default")
      (node (ref "IC15") (pin "3") (pinfunction "EN_3") (pintype "passive"))
      (node (ref "R80") (pin "1") (pintype "passive"))
      (node (ref "R81") (pin "2") (pintype "passive"))
      (node (ref "R83") (pin "2") (pintype "passive"))
    )
    (net (code "55") (name "Net-(IC15-ILIM)") (class "Default")
      (node (ref "IC15") (pin "5") (pinfunction "ILIM_5") (pintype "passive"))
      (node (ref "R84") (pin "2") (pintype "passive"))
    )
    (net (code "56") (name "Net-(IC15-OUT)") (class "Default")
      (node (ref "C54") (pin "1") (pinfunction "1_1") (pintype "passive"))
      (node (ref "IC15") (pin "6") (pinfunction "OUT_6") (pintype "passive"))
      (node (ref "L8") (pin "1") (pintype "passive"))
    )
    (net (code "57") (name "Net-(IC15-~{FLAG})") (class "Default")
      (node (ref "IC15") (pin "4") (pinfunction "~{FLAG}_4") (pintype "passive"))
      (node (ref "LED1") (pin "K") (pinfunction "K_K") (pintype "passive"))
    )
    (net (code "58") (name "Net-(IC16-VOUT)") (class "Default")
      (node (ref "C60") (pin "2") (pinfunction "2_2") (pintype "passive"))
      (node (ref "IC16") (pin "5") (pinfunction "VOUT_5") (pintype "passive"))
      (node (ref "R85") (pin "1") (pintype "passive"))
    )
    (net (code "59") (name "Net-(IC17-CURRENT_MODE)") (class "Default")
      (node (ref "IC17") (pin "3") (pinfunction "CURRENT_MODE_3") (pintype "passive"))
      (node (ref "R89") (pin "2") (pintype "passive"))
    )
    (net (code "60") (name "Net-(IC17-DIR)") (class "Default")
      (node (ref "IC17") (pin "11") (pinfunction "DIR_11") (pintype "passive"))
      (node (ref "R88") (pin "1") (pintype "passive"))
    )
    (net (code "61") (name "Net-(IC17-ENn_CC)") (class "Default")
      (node (ref "IC17") (pin "29") (pinfunction "ENn_CC_29") (pintype "passive"))
      (node (ref "R92") (pin "2") (pintype "passive"))
    )
    (net (code "62") (name "Net-(IC17-PORT)") (class "Default")
      (node (ref "IC17") (pin "4") (pinfunction "PORT_4") (pintype "passive"))
      (node (ref "R90") (pin "2") (pintype "passive"))
    )
    (net (code "63") (name "Net-(IC17-VBUS_DET)") (class "Default")
      (node (ref "IC17") (pin "5") (pinfunction "VBUS_DET_5") (pintype "passive"))
      (node (ref "R86") (pin "1") (pintype "passive"))
    )
    (net (code "64") (name "Net-(J7-VCC)") (class "Default")
      (node (ref "J7") (pin "1") (pinfunction "VCC_1") (pintype "power_in"))
      (node (ref "L7") (pin "1") (pintype "passive"))
    )
    (net (code "65") (name "Net-(J8-SBU2)") (class "Default")
      (node (ref "J8") (pin "B8") (pinfunction "SBU2_B8") (pintype "passive"))
      (node (ref "TP39") (pin "1") (pintype "passive"))
    )
    (net (code "66") (name "Net-(J9-ID)") (class "Default")
      (node (ref "J9") (pin "4") (pinfunction "ID_4") (pintype "passive"))
      (node (ref "TP41") (pin "1") (pintype "passive"))
    )
    (net (code "67") (name "Net-(LED1-PadA)") (class "Default")
      (node (ref "LED1") (pin "A") (pinfunction "A_A") (pintype "passive"))
      (node (ref "R79") (pin "1") (pintype "passive"))
    )
    (net (code "68") (name "Net-(Q1-D)") (class "Default")
      (node (ref "Q1") (pin "3") (pinfunction "D_3") (pintype "passive"))
      (node (ref "R81") (pin "1") (pintype "passive"))
    )
    (net (code "69") (name "Net-(Q2-G)") (class "Default")
      (node (ref "Q2") (pin "1") (pinfunction "G_1") (pintype "passive"))
      (node (ref "R109") (pin "2") (pintype "passive"))
      (node (ref "R110") (pin "2") (pintype "passive"))
    )
    (net (code "70") (name "SHIELD") (class "Default")
      (node (ref "J7") (pin "S") (pinfunction "SHIELD_S") (pintype "passive"))
    )
    (net (code "71") (name "SHIELD_OTG") (class "Default")
      (node (ref "J9") (pin "S") (pinfunction "SHIELD_S") (pintype "passive"))
      (node (ref "L9") (pin "1") (pintype "passive"))
    )
    (net (code "72") (name "USBC_VBUS") (class "Default")
      (node (ref "C63") (pin "2") (pinfunction "2_2") (pintype "passive"))
      (node (ref "J8") (pin "A4") (pinfunction "VBUS_A4") (pintype "passive"))
      (node (ref "J8") (pin "A9") (pinfunction "VBUS_A9") (pintype "passive"))
      (node (ref "J8") (pin "B4") (pinfunction "VBUS_B4") (pintype "passive"))
      (node (ref "J8") (pin "B9") (pinfunction "VBUS_B9") (pintype "passive"))
      (node (ref "L8") (pin "2") (pintype "passive"))
      (node (ref "R76") (pin "1") (pintype "passive"))
      (node (ref "R86") (pin "2") (pintype "passive"))
    )
    (net (code "73") (name "unconnected-(IC14-CBUS0-Pad22)") (class "Default")
      (node (ref "IC14") (pin "22") (pinfunction "CBUS0_22") (pintype "bidirectional+no_connect"))
    )
    (net (code "74") (name "unconnected-(IC14-CBUS1-Pad21)") (class "Default")
      (node (ref "IC14") (pin "21") (pinfunction "CBUS1_21") (pintype "bidirectional+no_connect"))
    )
    (net (code "75") (name "unconnected-(IC14-CBUS2-Pad10)") (class "Default")
      (node (ref "IC14") (pin "10") (pinfunction "CBUS2_10") (pintype "bidirectional+no_connect"))
    )
    (net (code "76") (name "unconnected-(IC14-CBUS3-Pad11)") (class "Default")
      (node (ref "IC14") (pin "11") (pinfunction "CBUS3_11") (pintype "bidirectional+no_connect"))
    )
    (net (code "77") (name "unconnected-(IC14-CBUS4-Pad9)") (class "Default")
      (node (ref "IC14") (pin "9") (pinfunction "CBUS4_9") (pintype "bidirectional+no_connect"))
    )
    (net (code "78") (name "unconnected-(IC14-CTS#-Pad8)") (class "Default")
      (node (ref "IC14") (pin "8") (pinfunction "CTS#_8") (pintype "input+no_connect"))
    )
    (net (code "79") (name "unconnected-(IC14-DCD#-Pad7)") (class "Default")
      (node (ref "IC14") (pin "7") (pinfunction "DCD#_7") (pintype "input+no_connect"))
    )
    (net (code "80") (name "unconnected-(IC14-DSR#-Pad6)") (class "Default")
      (node (ref "IC14") (pin "6") (pinfunction "DSR#_6") (pintype "input+no_connect"))
    )
    (net (code "81") (name "unconnected-(IC14-DTR#-Pad31)") (class "Default")
      (node (ref "IC14") (pin "31") (pinfunction "DTR#_31") (pintype "output+no_connect"))
    )
    (net (code "82") (name "unconnected-(IC14-OSCI-Pad27)") (class "Default")
      (node (ref "IC14") (pin "27") (pinfunction "OSCI_27") (pintype "input+no_connect"))
    )
    (net (code "83") (name "unconnected-(IC14-OSCO-Pad28)") (class "Default")
      (node (ref "IC14") (pin "28") (pinfunction "OSCO_28") (pintype "output+no_connect"))
    )
    (net (code "84") (name "unconnected-(IC14-RESET#-Pad18)") (class "Default")
      (node (ref "IC14") (pin "18") (pinfunction "RESET#_18") (pintype "input+no_connect"))
    )
    (net (code "85") (name "unconnected-(IC14-RI#-Pad3)") (class "Default")
      (node (ref "IC14") (pin "3") (pinfunction "RI#_3") (pintype "input+no_connect"))
    )
    (net (code "86") (name "unconnected-(IC14-RTS#-Pad32)") (class "Default")
      (node (ref "IC14") (pin "32") (pinfunction "RTS#_32") (pintype "output+no_connect"))
    )
    (net (code "87") (name "unconnected-(J7-ID-Pad4)") (class "Default")
      (node (ref "J7") (pin "4") (pinfunction "ID_4") (pintype "passive+no_connect"))
    )
    (net (code "88") (name "unconnected-(J8-SBU1-PadA8)") (class "Default")
      (node (ref "J8") (pin "A8") (pinfunction "SBU1_A8") (pintype "passive"))
    )
  )
)
